# H38R01.net
KiCad netlist of a schematic drawn in EAGLE
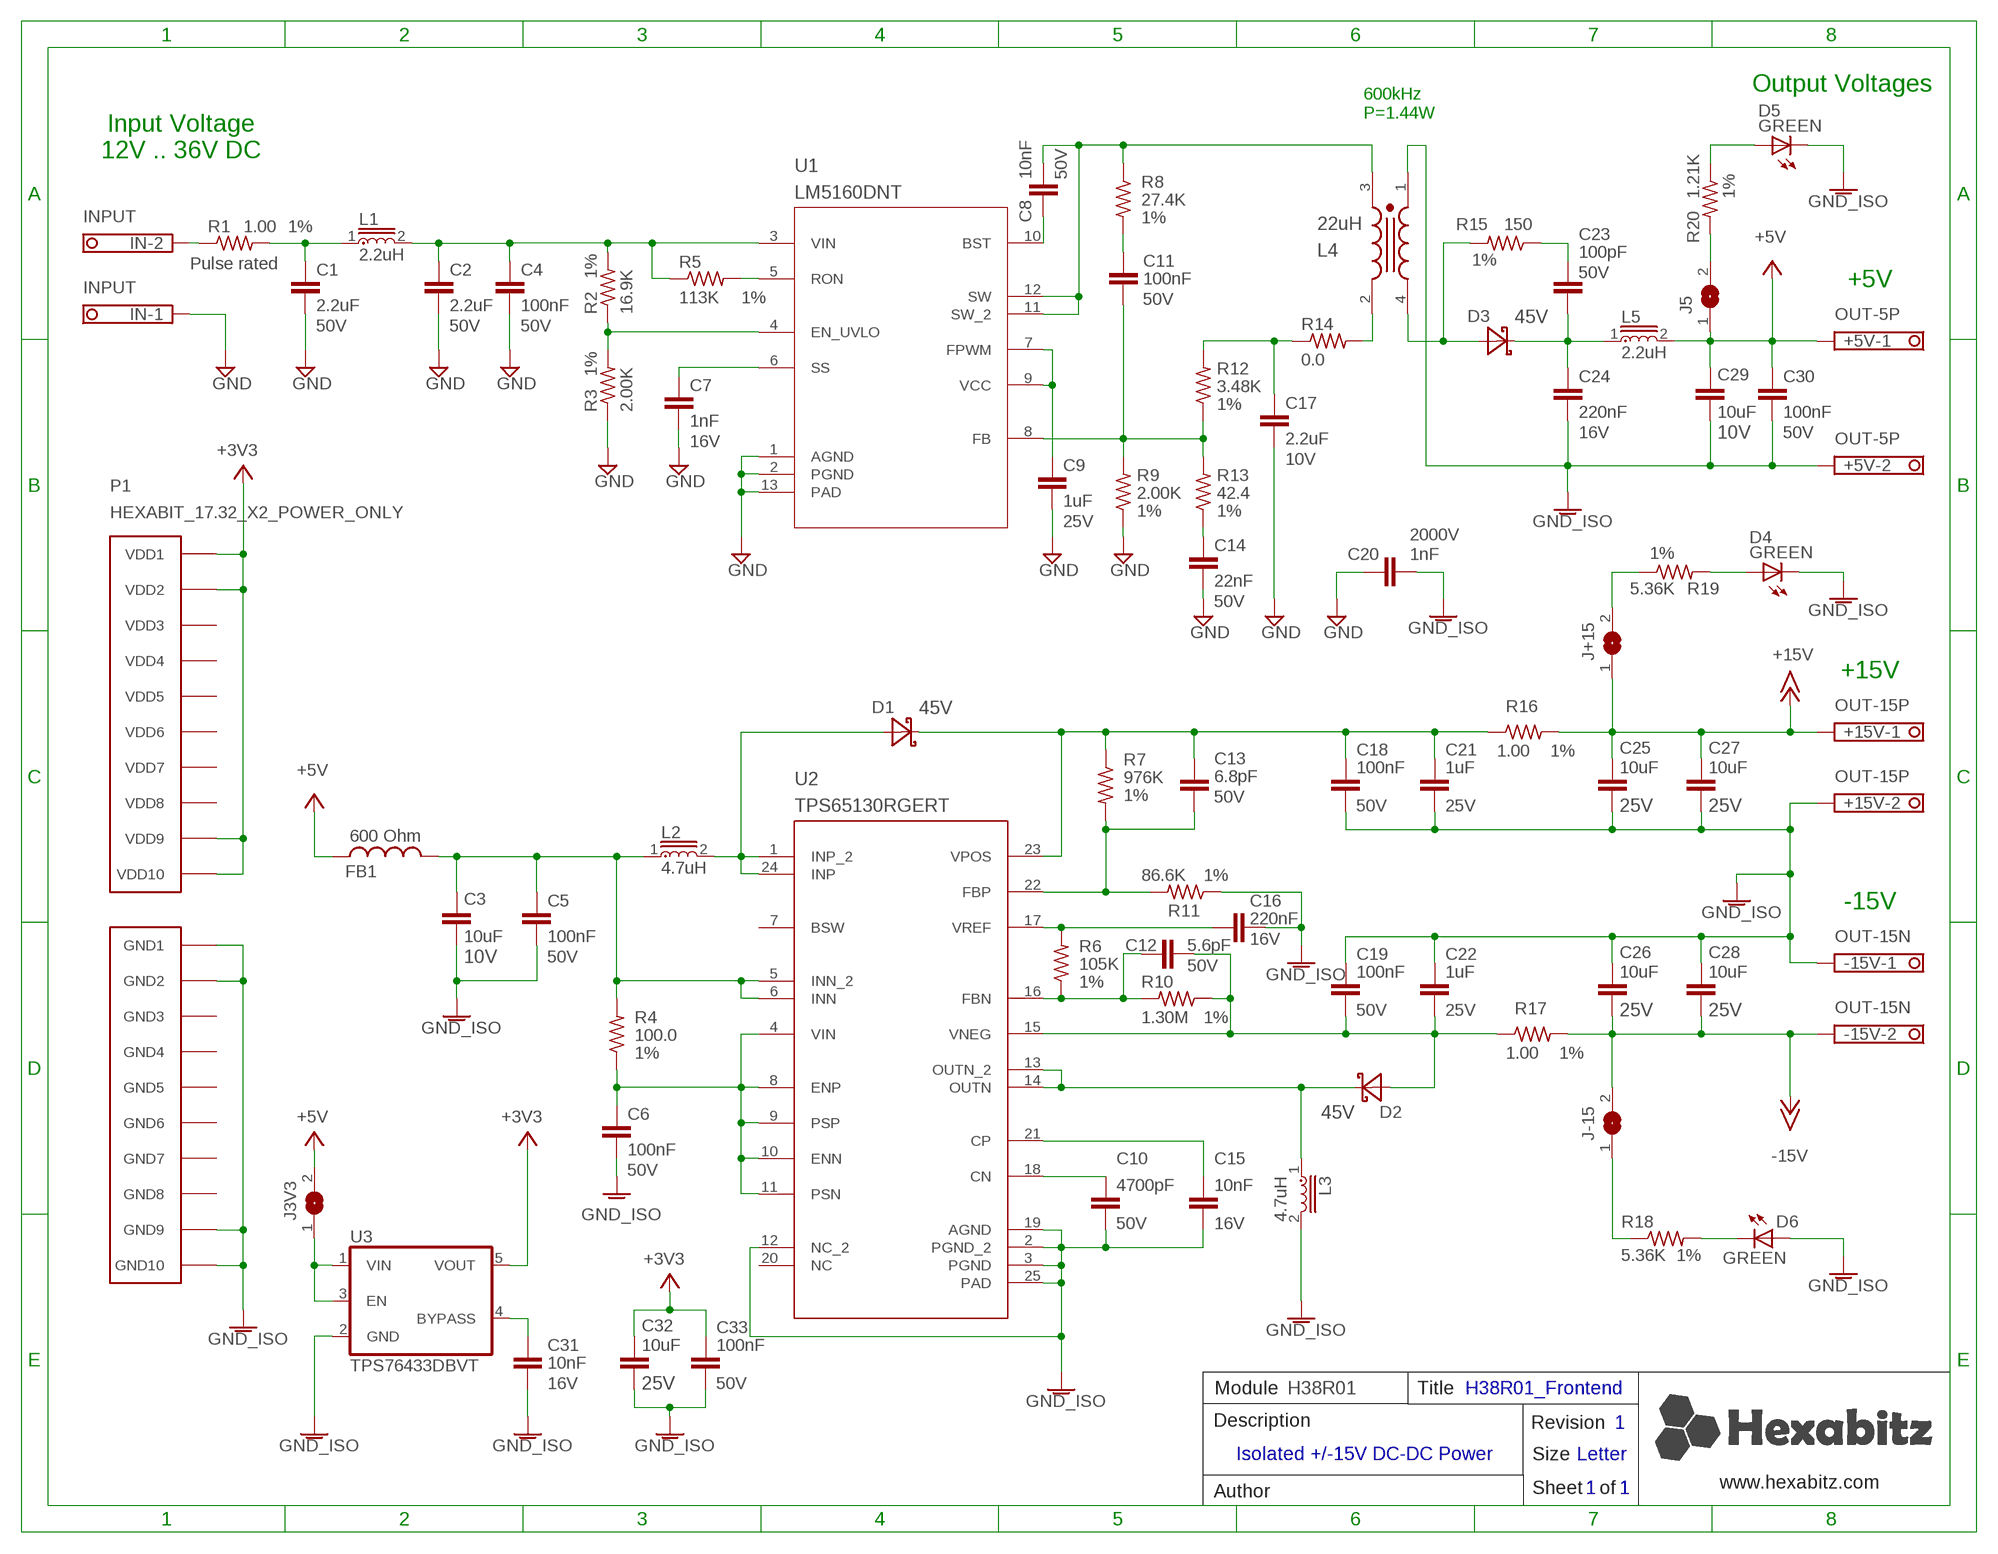
[diagram p0: schematic, sheet 1]

(export (version "E")
  (design (tool "Eeschema 10.0.6"))
  (components
    (comp (ref "+5V")
      (value "OUT-5P")
      (footprint "eagle-import:CON-PHOENIX-350_1751248")
      (fields (field (name "MPN") "1751251"))
      (libsource (lib "eagle-import") (part "CON-PHOENIX-350_1751248"))
    )
    (comp (ref "+15V")
      (value "OUT-15P")
      (footprint "eagle-import:CON-PHOENIX-350_1751248")
      (fields (field (name "MPN") "1751251"))
      (libsource (lib "eagle-import") (part "CON-PHOENIX-350_1751248"))
    )
    (comp (ref "-15V")
      (value "OUT-15N")
      (footprint "eagle-import:CON-PHOENIX-350_1751248")
      (fields (field (name "MPN") "1751251"))
      (libsource (lib "eagle-import") (part "CON-PHOENIX-350_1751248"))
    )
    (comp (ref "C1")
      (value "2.2uF")
      (footprint "eagle-import:C1206K")
      (fields (field (name "MPN") "UMK316B7225KD-T") (field (name "VOLTAGE") "50V"))
      (libsource (lib "eagle-import") (part "C-1206"))
    )
    (comp (ref "C2")
      (value "2.2uF")
      (footprint "eagle-import:C1206K")
      (fields (field (name "MPN") "UMK316B7225KD-T") (field (name "VOLTAGE") "50V"))
      (libsource (lib "eagle-import") (part "C-1206"))
    )
    (comp (ref "C3")
      (value "10uF")
      (footprint "eagle-import:C-0805")
      (fields
        (field (name "CAPACITANCE") "10uF")
        (field (name "MFN") "Würth Elektronik")
        (field (name "MPN") "885012207026")
        (field (name "OCTOPART_URL") "https://octopart.com/885012207026-w%C3%BCrth+elektronik-65419800?r=sp&s=PJ8-ZxRrRL-RXf1D2e7V7w ")
        (field (name "TOLERANCE") "10%")
        (field (name "VOLTAGE_RATING") "10V")
      )
      (libsource (lib "eagle-import") (part "C-0805"))
    )
    (comp (ref "C4")
      (value "100nF")
      (footprint "eagle-import:C-0603")
      (fields
        (field (name "CAPACITANCE") "100nF")
        (field (name "MFN") "TDK")
        (field (name "MPN") "C1608X7R1H104K")
        (field (name "OCTOPART_URL") "https://octopart.com/c1608x7r1h104k080aa-tdk-25947665?r=sp&s=vJ3_28x5RGekN18MBHqpKw")
        (field (name "TOLERANCE") "10%")
        (field (name "VOLTAGE_RATING") "50V")
      )
      (libsource (lib "eagle-import") (part "C-0603"))
    )
    (comp (ref "C5")
      (value "100nF")
      (footprint "eagle-import:C-0603")
      (fields
        (field (name "CAPACITANCE") "100nF")
        (field (name "MFN") "TDK")
        (field (name "MPN") "C1608X7R1H104K")
        (field (name "OCTOPART_URL") "https://octopart.com/c1608x7r1h104k080aa-tdk-25947665?r=sp&s=vJ3_28x5RGekN18MBHqpKw")
        (field (name "TOLERANCE") "10%")
        (field (name "VOLTAGE_RATING") "50V")
      )
      (libsource (lib "eagle-import") (part "C-0603"))
    )
    (comp (ref "C6")
      (value "100nF")
      (footprint "eagle-import:C-0603")
      (fields
        (field (name "CAPACITANCE") "100nF")
        (field (name "MFN") "TDK")
        (field (name "MPN") "C1608X7R1H104K")
        (field (name "OCTOPART_URL") "https://octopart.com/c1608x7r1h104k080aa-tdk-25947665?r=sp&s=vJ3_28x5RGekN18MBHqpKw")
        (field (name "TOLERANCE") "10%")
        (field (name "VOLTAGE_RATING") "50V")
      )
      (libsource (lib "eagle-import") (part "C-0603"))
    )
    (comp (ref "C7")
      (value "1nF")
      (footprint "eagle-import:C-0603")
      (fields
        (field (name "CAPACITANCE") "1nF")
        (field (name "MFN") "Würth Elektronik")
        (field (name "MPN") "885012206034")
        (field (name "OCTOPART_URL") "https://octopart.com/885012206034-w%C3%BCrth+elektronik-53914743?r=sp&s=3y92xzxLSKK6IudBxcGU8w")
        (field (name "TOLERANCE") "10%")
        (field (name "VOLTAGE_RATING") "16V")
      )
      (libsource (lib "eagle-import") (part "C-0603"))
    )
    (comp (ref "C8")
      (value "10nF")
      (footprint "eagle-import:C-0603")
      (fields
        (field (name "CAPACITANCE") "10nF")
        (field (name "MFN") "KEMET")
        (field (name "MPN") "C0603C103J5RACTU")
        (field (name "OCTOPART_URL") "https://octopart.com/c0603c103j5ractu-kemet-91371?r=sp&s=Kyc2xDn-SuWGmNLJldLSIQ")
        (field (name "TOLERANCE") "10%")
        (field (name "VOLTAGE_RATING") "50V")
      )
      (libsource (lib "eagle-import") (part "C-0603"))
    )
    (comp (ref "C9")
      (value "1uF")
      (footprint "eagle-import:C-0603")
      (fields
        (field (name "CAPACITANCE") "1uF")
        (field (name "MFN") "Taiyo Yuden")
        (field (name "MPN") "TMK107B7105KA-T")
        (field (name "OCTOPART_URL") "https://octopart.com/tmk107b7105ka-t-taiyo+yuden-20363789?r=sp&s=C0MvDSixSxq0oU7K_M5ppQ")
        (field (name "TOLERANCE") "10%")
        (field (name "VOLTAGE_RATING") "25V")
      )
      (libsource (lib "eagle-import") (part "C-0603"))
    )
    (comp (ref "C10")
      (value "4700pF")
      (footprint "eagle-import:C-0603")
      (fields
        (field (name "CAPACITANCE") "4700pF")
        (field (name "MFN") "Würth Elektronik")
        (field (name "MPN") "885012206087")
        (field (name "OCTOPART_URL") "https://octopart.com/885012206087-w%C3%BCrth+elektronik-53914796?r=sp&s=1K2nhhCgSUq-KN0bvB69Uw")
        (field (name "TOLERANCE") "10%")
        (field (name "VOLTAGE_RATING") "50V")
      )
      (libsource (lib "eagle-import") (part "C-0603"))
    )
    (comp (ref "C11")
      (value "100nF")
      (footprint "eagle-import:C-0603")
      (fields
        (field (name "CAPACITANCE") "100nF")
        (field (name "MFN") "TDK")
        (field (name "MPN") "C1608X7R1H104K")
        (field (name "OCTOPART_URL") "https://octopart.com/c1608x7r1h104k080aa-tdk-25947665?r=sp&s=vJ3_28x5RGekN18MBHqpKw")
        (field (name "TOLERANCE") "10%")
        (field (name "VOLTAGE_RATING") "50V")
      )
      (libsource (lib "eagle-import") (part "C-0603"))
    )
    (comp (ref "C12")
      (value "5.6pF")
      (footprint "eagle-import:C-0603")
      (fields
        (field (name "CAPACITANCE") "5.6pF")
        (field (name "MFN") "TDK")
        (field (name "MPN") "06035A5R6CAT2A")
        (field (name "OCTOPART_URL") "https://octopart.com/06035a5r6cat2a-avx-194782?r=sp&s=arSRmqwrS2KePu_erVaGmg")
        (field (name "TOLERANCE") "5%")
        (field (name "VOLTAGE_RATING") "50V")
      )
      (libsource (lib "eagle-import") (part "C-0603"))
    )
    (comp (ref "C13")
      (value "6.8pF")
      (footprint "eagle-import:C-0603")
      (fields
        (field (name "CAPACITANCE") "6.8pF")
        (field (name "MFN") "AVX")
        (field (name "MPN") "06035A6R8CAT2A")
        (field (name "OCTOPART_URL") "https://octopart.com/06035a6r8cat2a-avx-194783?r=sp&s=5-5NBtM6RDWLTSW9K30eVg")
        (field (name "TOLERANCE") "10%")
        (field (name "VOLTAGE_RATING") "50V")
      )
      (libsource (lib "eagle-import") (part "C-0603"))
    )
    (comp (ref "C14")
      (value "22nF")
      (footprint "eagle-import:C-0603")
      (fields
        (field (name "CAPACITANCE") "22nF")
        (field (name "MFN") "Murata")
        (field (name "MPN") "GRM188R71H223KA01D")
        (field (name "OCTOPART_URL") "https://octopart.com/grm188r71h223ka01d-murata-196232?r=sp&s=t23e6pi9S5yo9EHFMT_EKg")
        (field (name "TOLERANCE") "10%")
        (field (name "VOLTAGE_RATING") "50V")
      )
      (libsource (lib "eagle-import") (part "C-0603"))
    )
    (comp (ref "C15")
      (value "10nF")
      (footprint "eagle-import:C-0603")
      (fields
        (field (name "CAPACITANCE") "10nF")
        (field (name "MFN") "Würth Elektronik")
        (field (name "MPN") "885012206040")
        (field (name "OCTOPART_URL") "https://octopart.com/885012206040-w%C3%BCrth+elektronik-53914749?r=sp&s=G3_ezLbARM2-FohtMFECqg")
        (field (name "TOLERANCE") "10%")
        (field (name "VOLTAGE_RATING") "16V")
      )
      (libsource (lib "eagle-import") (part "C-0603"))
    )
    (comp (ref "C16")
      (value "220nF")
      (footprint "eagle-import:C-0603")
      (fields
        (field (name "CAPACITANCE") "220nF")
        (field (name "MFN") "Würth Elektronik")
        (field (name "MPN") "885012206048")
        (field (name "OCTOPART_URL") "https://octopart.com/885012206048-w%C3%BCrth+elektronik-53914757?r=sp&s=r2jVh1M7TTWSNtdrsMd35A")
        (field (name "TOLERANCE") "10%")
        (field (name "VOLTAGE_RATING") "16V")
      )
      (libsource (lib "eagle-import") (part "C-0603"))
    )
    (comp (ref "C17")
      (value "2.2uF")
      (footprint "eagle-import:C-0603")
      (fields
        (field (name "CAPACITANCE") "2.2uF")
        (field (name "MFN") "Murata")
        (field (name "MPN") "GRM188R71A225KE15D")
        (field (name "OCTOPART_URL") "https://octopart.com/grm188r71a225ke15d-murata-197889?r=sp&s=UhC5vs9xSQGkDEPPXrg6Ig")
        (field (name "TOLERANCE") "10%")
        (field (name "VOLTAGE_RATING") "10V")
      )
      (libsource (lib "eagle-import") (part "C-0603"))
    )
    (comp (ref "C18")
      (value "100nF")
      (footprint "eagle-import:C-0603")
      (fields
        (field (name "CAPACITANCE") "100nF")
        (field (name "MFN") "TDK")
        (field (name "MPN") "C1608X7R1H104K")
        (field (name "OCTOPART_URL") "https://octopart.com/c1608x7r1h104k080aa-tdk-25947665?r=sp&s=vJ3_28x5RGekN18MBHqpKw")
        (field (name "TOLERANCE") "10%")
        (field (name "VOLTAGE_RATING") "50V")
      )
      (libsource (lib "eagle-import") (part "C-0603"))
    )
    (comp (ref "C19")
      (value "100nF")
      (footprint "eagle-import:C-0603")
      (fields
        (field (name "CAPACITANCE") "100nF")
        (field (name "MFN") "TDK")
        (field (name "MPN") "C1608X7R1H104K")
        (field (name "OCTOPART_URL") "https://octopart.com/c1608x7r1h104k080aa-tdk-25947665?r=sp&s=vJ3_28x5RGekN18MBHqpKw")
        (field (name "TOLERANCE") "10%")
        (field (name "VOLTAGE_RATING") "50V")
      )
      (libsource (lib "eagle-import") (part "C-0603"))
    )
    (comp (ref "C20")
      (value "1nF")
      (footprint "eagle-import:C1206K")
      (fields (field (name "MPN") "202R18W102KV4E") (field (name "VOLTAGE") "2000V"))
      (libsource (lib "eagle-import") (part "C-1206"))
    )
    (comp (ref "C21")
      (value "1uF")
      (footprint "eagle-import:C-0603")
      (fields
        (field (name "CAPACITANCE") "1uF")
        (field (name "MFN") "Taiyo Yuden")
        (field (name "MPN") "TMK107B7105KA-T")
        (field (name "OCTOPART_URL") "https://octopart.com/tmk107b7105ka-t-taiyo+yuden-20363789?r=sp&s=C0MvDSixSxq0oU7K_M5ppQ")
        (field (name "TOLERANCE") "10%")
        (field (name "VOLTAGE_RATING") "25V")
      )
      (libsource (lib "eagle-import") (part "C-0603"))
    )
    (comp (ref "C22")
      (value "1uF")
      (footprint "eagle-import:C-0603")
      (fields
        (field (name "CAPACITANCE") "1uF")
        (field (name "MFN") "Taiyo Yuden")
        (field (name "MPN") "TMK107B7105KA-T")
        (field (name "OCTOPART_URL") "https://octopart.com/tmk107b7105ka-t-taiyo+yuden-20363789?r=sp&s=C0MvDSixSxq0oU7K_M5ppQ")
        (field (name "TOLERANCE") "10%")
        (field (name "VOLTAGE_RATING") "25V")
      )
      (libsource (lib "eagle-import") (part "C-0603"))
    )
    (comp (ref "C23")
      (value "100pF")
      (footprint "eagle-import:C-0603")
      (fields
        (field (name "CAPACITANCE") "100pF")
        (field (name "MFN") "KEMET")
        (field (name "MPN") "C0603C101J5GACTU")
        (field (name "OCTOPART_URL") "https://octopart.com/c0603c101j5gactu-kemet-100052?r=sp&s=G9Wafbc2Rs-t41DcITu08w")
        (field (name "TOLERANCE") "5%")
        (field (name "VOLTAGE_RATING") "50V")
      )
      (libsource (lib "eagle-import") (part "C-0603"))
    )
    (comp (ref "C24")
      (value "220nF")
      (footprint "eagle-import:C-0603")
      (fields
        (field (name "CAPACITANCE") "220nF")
        (field (name "MFN") "Würth Elektronik")
        (field (name "MPN") "885012206048")
        (field (name "OCTOPART_URL") "https://octopart.com/885012206048-w%C3%BCrth+elektronik-53914757?r=sp&s=r2jVh1M7TTWSNtdrsMd35A")
        (field (name "TOLERANCE") "10%")
        (field (name "VOLTAGE_RATING") "16V")
      )
      (libsource (lib "eagle-import") (part "C-0603"))
    )
    (comp (ref "C25")
      (value "10uF")
      (footprint "eagle-import:C-0805")
      (fields
        (field (name "CAPACITANCE") "10uF")
        (field (name "MFN") "Murata")
        (field (name "MPN") "GRM21BC71E106KE11L")
        (field (name "OCTOPART_URL") "https://octopart.com/grm21bc71e106ke11l-murata-51454492?r=sp&s=2Vde2RpCRyqy5YYMvYke3Q ")
        (field (name "TOLERANCE") "10%")
        (field (name "VOLTAGE_RATING") "25V")
      )
      (libsource (lib "eagle-import") (part "C-0805"))
    )
    (comp (ref "C26")
      (value "10uF")
      (footprint "eagle-import:C-0805")
      (fields
        (field (name "CAPACITANCE") "10uF")
        (field (name "MFN") "Murata")
        (field (name "MPN") "GRM21BC71E106KE11L")
        (field (name "OCTOPART_URL") "https://octopart.com/grm21bc71e106ke11l-murata-51454492?r=sp&s=2Vde2RpCRyqy5YYMvYke3Q ")
        (field (name "TOLERANCE") "10%")
        (field (name "VOLTAGE_RATING") "25V")
      )
      (libsource (lib "eagle-import") (part "C-0805"))
    )
    (comp (ref "C27")
      (value "10uF")
      (footprint "eagle-import:C-0805")
      (fields
        (field (name "CAPACITANCE") "10uF")
        (field (name "MFN") "Murata")
        (field (name "MPN") "GRM21BC71E106KE11L")
        (field (name "OCTOPART_URL") "https://octopart.com/grm21bc71e106ke11l-murata-51454492?r=sp&s=2Vde2RpCRyqy5YYMvYke3Q ")
        (field (name "TOLERANCE") "10%")
        (field (name "VOLTAGE_RATING") "25V")
      )
      (libsource (lib "eagle-import") (part "C-0805"))
    )
    (comp (ref "C28")
      (value "10uF")
      (footprint "eagle-import:C-0805")
      (fields
        (field (name "CAPACITANCE") "10uF")
        (field (name "MFN") "Murata")
        (field (name "MPN") "GRM21BC71E106KE11L")
        (field (name "OCTOPART_URL") "https://octopart.com/grm21bc71e106ke11l-murata-51454492?r=sp&s=2Vde2RpCRyqy5YYMvYke3Q")
        (field (name "TOLERANCE") "10%")
        (field (name "VOLTAGE_RATING") "25V")
      )
      (libsource (lib "eagle-import") (part "C-0805"))
    )
    (comp (ref "C29")
      (value "10uF")
      (footprint "eagle-import:C-0805")
      (fields
        (field (name "CAPACITANCE") "10uF")
        (field (name "MFN") "Würth Elektronik")
        (field (name "MPN") "885012207026")
        (field (name "OCTOPART_URL") "https://octopart.com/885012207026-w%C3%BCrth+elektronik-65419800?r=sp&s=PJ8-ZxRrRL-RXf1D2e7V7w")
        (field (name "TOLERANCE") "10%")
        (field (name "VOLTAGE_RATING") "10V")
      )
      (libsource (lib "eagle-import") (part "C-0805"))
    )
    (comp (ref "C30")
      (value "100nF")
      (footprint "eagle-import:C-0603")
      (fields
        (field (name "CAPACITANCE") "100nF")
        (field (name "MFN") "TDK")
        (field (name "MPN") "C1608X7R1H104K")
        (field (name "OCTOPART_URL") "https://octopart.com/c1608x7r1h104k080aa-tdk-25947665?r=sp&s=vJ3_28x5RGekN18MBHqpKw")
        (field (name "TOLERANCE") "10%")
        (field (name "VOLTAGE_RATING") "50V")
      )
      (libsource (lib "eagle-import") (part "C-0603"))
    )
    (comp (ref "C31")
      (value "10nF")
      (footprint "eagle-import:C-0603")
      (fields
        (field (name "CAPACITANCE") "10nF")
        (field (name "MFN") "Würth Elektronik")
        (field (name "MPN") "885012206040")
        (field (name "OCTOPART_URL") "https://octopart.com/885012206040-w%C3%BCrth+elektronik-53914749?r=sp&s=G3_ezLbARM2-FohtMFECqg")
        (field (name "TOLERANCE") "10%")
        (field (name "VOLTAGE_RATING") "16V")
      )
      (libsource (lib "eagle-import") (part "C-0603"))
    )
    (comp (ref "C32")
      (value "10uF")
      (footprint "eagle-import:C-0805")
      (fields
        (field (name "CAPACITANCE") "10uF")
        (field (name "MFN") "Murata")
        (field (name "MPN") "GRM21BC71E106KE11L")
        (field (name "OCTOPART_URL") "https://octopart.com/grm21bc71e106ke11l-murata-51454492?r=sp&s=2Vde2RpCRyqy5YYMvYke3Q")
        (field (name "TOLERANCE") "10%")
        (field (name "VOLTAGE_RATING") "25V")
      )
      (libsource (lib "eagle-import") (part "C-0805"))
    )
    (comp (ref "C33")
      (value "100nF")
      (footprint "eagle-import:C-0603")
      (fields
        (field (name "CAPACITANCE") "100nF")
        (field (name "MFN") "TDK")
        (field (name "MPN") "C1608X7R1H104K")
        (field (name "OCTOPART_URL") "https://octopart.com/c1608x7r1h104k080aa-tdk-25947665?r=sp&s=vJ3_28x5RGekN18MBHqpKw")
        (field (name "TOLERANCE") "10%")
        (field (name "VOLTAGE_RATING") "50V")
      )
      (libsource (lib "eagle-import") (part "C-0603"))
    )
    (comp (ref "D1")
      (value "DIOD-SOD-123")
      (footprint "eagle-import:SOD123")
      (fields
        (field (name "MFN") "ON Semiconductor")
        (field (name "MPN") "NTS245SFT1G")
        (field (name "OCTOPART_URL") "https://octopart.com/nts245sft1g-on+semiconductor-53638116?r=sp&s=Zo8Z59f0QcynsgZ2PtBRwg")
        (field (name "VOLTAGE_RATING_DC") "45V")
      )
      (libsource (lib "eagle-import") (part "DIOD-SOD-123"))
    )
    (comp (ref "D2")
      (value "DIOD-SOD-123")
      (footprint "eagle-import:SOD123")
      (fields
        (field (name "MFN") "ON Semiconductor")
        (field (name "MPN") "NTS245SFT1G")
        (field (name "OCTOPART_URL") "https://octopart.com/nts245sft1g-on+semiconductor-53638116?r=sp&s=Zo8Z59f0QcynsgZ2PtBRwg")
        (field (name "VOLTAGE_RATING_DC") "45V")
      )
      (libsource (lib "eagle-import") (part "DIOD-SOD-123"))
    )
    (comp (ref "D3")
      (value "DIOD-SOD-123")
      (footprint "eagle-import:SOD123")
      (fields
        (field (name "MFN") "ON Semiconductor")
        (field (name "MPN") "NTS245SFT1G")
        (field (name "OCTOPART_URL") "https://octopart.com/nts245sft1g-on+semiconductor-53638116?r=sp&s=Zo8Z59f0QcynsgZ2PtBRwg")
        (field (name "VOLTAGE_RATING_DC") "45V")
      )
      (libsource (lib "eagle-import") (part "DIOD-SOD-123"))
    )
    (comp (ref "D4")
      (value "GREEN")
      (footprint "eagle-import:VLMS1300-GS08")
      (fields (field (name "MPN") "VLMTG1300-GS08"))
      (libsource (lib "eagle-import") (part "VLMTG1300-GS08"))
    )
    (comp (ref "D5")
      (value "GREEN")
      (footprint "eagle-import:VLMS1300-GS08")
      (fields (field (name "MPN") "VLMTG1300-GS08"))
      (libsource (lib "eagle-import") (part "VLMTG1300-GS08"))
    )
    (comp (ref "D6")
      (value "GREEN")
      (footprint "eagle-import:VLMS1300-GS08")
      (fields (field (name "MPN") "VLMTG1300-GS08"))
      (libsource (lib "eagle-import") (part "VLMTG1300-GS08"))
    )
    (comp (ref "FB1")
      (value "600 Ohm")
      (footprint "eagle-import:FB-0603")
      (fields
        (field (name "MFN") "Murata")
        (field (name "MPN") "BLM18KG601SN1D")
        (field (name "OCTOPART_URL") "https://octopart.com/blm18kg601sn1d-murata-12276433?r=sp&s=hc41AUOpRWisdZqqWWZOxA")
      )
      (libsource (lib "eagle-import") (part "FB-0603"))
    )
    (comp (ref "IN")
      (value "INPUT")
      (footprint "eagle-import:CON-PHOENIX-350_1751248")
      (fields (field (name "MPN") "1751251"))
      (libsource (lib "eagle-import") (part "CON-PHOENIX-350_1751248"))
    )
    (comp (ref "J+15")
      (value "SJ")
      (footprint "eagle-import:SJ")
      (libsource (lib "eagle-import") (part "SJ"))
    )
    (comp (ref "J-15")
      (value "SJ")
      (footprint "eagle-import:SJ")
      (libsource (lib "eagle-import") (part "SJ"))
    )
    (comp (ref "J3V3")
      (value "SJ")
      (footprint "eagle-import:SJ")
      (libsource (lib "eagle-import") (part "SJ"))
    )
    (comp (ref "J5") (value "SJ") (footprint "eagle-import:SJ") (libsource (lib "eagle-import") (part "SJ")))
    (comp (ref "L1")
      (value "2.2uH")
      (footprint "eagle-import:C-0603")
      (fields (field (name "MPN") "LQM18PN2R2MFHD"))
      (libsource (lib "eagle-import") (part "LQM18PN2R2MFHD"))
    )
    (comp (ref "L2")
      (value "4.7uH")
      (footprint "eagle-import:WUERTH_ELEKTRONIK_74404024100_0")
      (fields
        (field (name "MF") "Wuerth Elektronik")
        (field (name "MPN") "74404024100")
        (field (name "INDUCTANCE") "4.7μH")
        (field (name "MPN_1") "74404024047")
        (field (name "OCTOPART_URL") "https://octopart.com/74404024047-w%C3%BCrth+elektronik-46948230?r=sp")
      )
      (libsource (lib "eagle-import") (part "WUERTH_ELEKTRONIK_74404024100WUERTH_ELEKTRONIK_74404024100_0_0"))
    )
    (comp (ref "L3")
      (value "4.7uH")
      (footprint "eagle-import:WUERTH_ELEKTRONIK_74404024100_0")
      (fields
        (field (name "MF") "Wuerth Elektronik")
        (field (name "MPN") "74404024100")
        (field (name "INDUCTANCE") "4.7μH")
        (field (name "MPN_1") "74404024047")
        (field (name "OCTOPART_URL") "https://octopart.com/74404024047-w%C3%BCrth+elektronik-46948230?r=sp")
      )
      (libsource (lib "eagle-import") (part "WUERTH_ELEKTRONIK_74404024100WUERTH_ELEKTRONIK_74404024100_0_0"))
    )
    (comp (ref "L4")
      (value "22uH")
      (footprint "eagle-import:WUERTH_ELEKTRONIK_74489430220_0")
      (fields (field (name "MF") "Wuerth Elektronik") (field (name "MPN") "74489430220"))
      (libsource (lib "eagle-import") (part "WUERTH_ELEKTRONIK_74489430220WUERTH_ELEKTRONIK_74489430220_0_0"))
    )
    (comp (ref "L5")
      (value "2.2uH")
      (footprint "eagle-import:C-0603")
      (fields (field (name "MPN") "LQM18PN2R2MFHD"))
      (libsource (lib "eagle-import") (part "LQM18PN2R2MFHD"))
    )
    (comp (ref "P1")
      (value "HEXABIT_17.32_X2_POWER_ONLY")
      (footprint "eagle-import:HEXABIT_17.32_X2_POWER_ONLY")
      (libsource (lib "eagle-import") (part "HEXABIT_?_X2_POWER_ONLY17.32"))
    )
    (comp (ref "R1")
      (value "1.00")
      (footprint "eagle-import:R-0603")
      (fields
        (field (name "MFN") "Vishay")
        (field (name "MPN") "RCS06031R00FKEA")
        (field (name "OCTOPART_URL") "https://octopart.com/rcs06031r00fkea-vishay-75198106?r=sp")
        (field (name "RESISTANCE") "1.00")
        (field (name "TOLERANCE") "1%")
      )
      (libsource (lib "eagle-import") (part "R-0603"))
    )
    (comp (ref "R2")
      (value "16.9K")
      (footprint "eagle-import:R-0603")
      (fields
        (field (name "MFN") "Vishay")
        (field (name "MPN") "CRCW060316K9FKEA")
        (field (name "OCTOPART_URL") "https://octopart.com/crcw060316k9fkea-vishay-39809405?r=sp&s=gpyoC5sESS275Bx1L_ovfA")
        (field (name "RESISTANCE") "16.9K")
        (field (name "TOLERANCE") "1%")
      )
      (libsource (lib "eagle-import") (part "R-0603"))
    )
    (comp (ref "R3")
      (value "2.00K")
      (footprint "eagle-import:R-0603")
      (fields
        (field (name "MFN") "Vishay")
        (field (name "MPN") "CRCW06032K00FKEA")
        (field (name "OCTOPART_URL") "https://octopart.com/crcw06032k00fkea-vishay-39455515?r=sp&s=oLMBsKnqSyiGxb37P4YGRQ")
        (field (name "RESISTANCE") "2.00k")
        (field (name "TOLERANCE") "1%")
      )
      (libsource (lib "eagle-import") (part "R-0603"))
    )
    (comp (ref "R4")
      (value "100.0")
      (footprint "eagle-import:R-0603")
      (fields
        (field (name "MFN") "Vishay")
        (field (name "MPN") "CRCW0603100RFKEA")
        (field (name "OCTOPART_URL") "https://octopart.com/crcw0603100rfkea-vishay-39454046?r=sp&s=ZCLXy-8WTNaYdj0NMUzO0A")
        (field (name "RESISTANCE") "100.0")
        (field (name "TOLERANCE") "1%")
      )
      (libsource (lib "eagle-import") (part "R-0603"))
    )
    (comp (ref "R5")
      (value "113K")
      (footprint "eagle-import:R-0603")
      (fields
        (field (name "MFN") "Vishay")
        (field (name "MPN") "CRCW0603113KFKEA")
        (field (name "OCTOPART_URL") "https://octopart.com/crcw0603113kfkea-vishay-39817257?r=sp&s=CTaWAi24RJSm7_6d5HDAcw")
        (field (name "RESISTANCE") "113K")
        (field (name "TOLERANCE") "1%")
      )
      (libsource (lib "eagle-import") (part "R-0603"))
    )
    (comp (ref "R6")
      (value "105K")
      (footprint "eagle-import:R-0603")
      (fields
        (field (name "MFN") "Vishay")
        (field (name "MPN") "CRCW0603105KFKEA")
        (field (name "OCTOPART_URL") "https://octopart.com/crcw0603105kfkea-vishay-39783419?r=sp&s=m57LqOW9SZi8auMTWgZAuA")
        (field (name "RESISTANCE") "105K")
        (field (name "TOLERANCE") "1%")
      )
      (libsource (lib "eagle-import") (part "R-0603"))
    )
    (comp (ref "R7")
      (value "976K")
      (footprint "eagle-import:R-0603")
      (fields
        (field (name "MFN") "Vishay")
        (field (name "MPN") "CRCW0603976KFKEA")
        (field (name "OCTOPART_URL") "https://octopart.com/crcw0603976kfkea-vishay-39847458?r=sp&s=cUxC9lyxRzee74EppCoygA")
        (field (name "RESISTANCE") "976K")
        (field (name "TOLERANCE") "1%")
      )
      (libsource (lib "eagle-import") (part "R-0603"))
    )
    (comp (ref "R8")
      (value "27.4K")
      (footprint "eagle-import:R-0603")
      (fields
        (field (name "MFN") "Vishay")
        (field (name "MPN") "CRCW060327K4FKEA")
        (field (name "OCTOPART_URL") "https://octopart.com/crcw060327k4fkea-vishay-40950191?r=sp&s=-sh_flwyTnabpVfO2SO3MQ")
        (field (name "RESISTANCE") "27.4K")
        (field (name "TOLERANCE") "1%")
      )
      (libsource (lib "eagle-import") (part "R-0603"))
    )
    (comp (ref "R9")
      (value "2.00K")
      (footprint "eagle-import:R-0603")
      (fields
        (field (name "MFN") "Vishay")
        (field (name "MPN") "CRCW06032K00FKEA")
        (field (name "OCTOPART_URL") "https://octopart.com/crcw06032k00fkea-vishay-39455515?r=sp&s=oLMBsKnqSyiGxb37P4YGRQ")
        (field (name "RESISTANCE") "2.00k")
        (field (name "TOLERANCE") "1%")
      )
      (libsource (lib "eagle-import") (part "R-0603"))
    )
    (comp (ref "R10")
      (value "1.30M")
      (footprint "eagle-import:R-0603")
      (fields
        (field (name "MFN") "Vishay")
        (field (name "MPN") "CRCW06031M30FKEA")
        (field (name "OCTOPART_URL") "https://octopart.com/crcw06031m30fkea-vishay-39601140?r=sp&s=IFmbrVO2QdmVcSmXO7E1AA")
        (field (name "RESISTANCE") "1.30M")
        (field (name "TOLERANCE") "1%")
      )
      (libsource (lib "eagle-import") (part "R-0603"))
    )
    (comp (ref "R11")
      (value "86.6K")
      (footprint "eagle-import:R-0603")
      (fields
        (field (name "MFN") "Vishay")
        (field (name "MPN") "CRCW060386K6FKEA")
        (field (name "OCTOPART_URL") "https://octopart.com/crcw060386k6fkea-vishay-39809057?r=sp&s=kiKKot43Sa6nkjOnoApb7Q")
        (field (name "RESISTANCE") "86.6K")
        (field (name "TOLERANCE") "1%")
      )
      (libsource (lib "eagle-import") (part "R-0603"))
    )
    (comp (ref "R12")
      (value "3.48K")
      (footprint "eagle-import:R-0603")
      (fields
        (field (name "MFN") "Vishay")
        (field (name "MPN") "CRCW06033K48FKEA")
        (field (name "OCTOPART_URL") "https://octopart.com/crcw06033k48fkea-vishay-39806638?r=sp&s=N5g7S2AyTDmMWBX-_wGc6Q")
        (field (name "RESISTANCE") "3.48K")
        (field (name "TOLERANCE") "1%")
      )
      (libsource (lib "eagle-import") (part "R-0603"))
    )
    (comp (ref "R13")
      (value "42.4")
      (footprint "eagle-import:R-0603")
      (fields
        (field (name "MFN") "Vishay")
        (field (name "MPN") "CRCW060342R2FKEA")
        (field (name "OCTOPART_URL") "https://octopart.com/crcw060342r2fkea-vishay-39808977?r=sp&s=-XoBdwS-TmODK1i1WGs3Gw")
        (field (name "RESISTANCE") "42.2R")
        (field (name "TOLERANCE") "1%")
      )
      (libsource (lib "eagle-import") (part "R-0603"))
    )
    (comp (ref "R14")
      (value "0.0")
      (footprint "eagle-import:R-0603")
      (fields
        (field (name "MFN") "Panasonic")
        (field (name "MPN") "ERJ-3GEY0R00V")
        (field (name "OCTOPART_URL") "https://octopart.com/erj-3gey0r00v-panasonic-55389238?r=sp&s=8dmrTZyCS32IAujh55Hh-g")
        (field (name "RESISTANCE") "0.0R")
        (field (name "TOLERANCE") "5%")
      )
      (libsource (lib "eagle-import") (part "R-0603"))
    )
    (comp (ref "R15")
      (value "150")
      (footprint "eagle-import:R-0603")
      (fields
        (field (name "MFN") "Vishay")
        (field (name "MPN") "CRCW0603150RFKEA")
        (field (name "OCTOPART_URL") "https://octopart.com/crcw0603150rfkea-vishay-39455211?r=sp&s=fhZ4fTqDSW-fVK_X4mehlA")
        (field (name "RESISTANCE") "150R")
        (field (name "TOLERANCE") "1%")
      )
      (libsource (lib "eagle-import") (part "R-0603"))
    )
    (comp (ref "R16")
      (value "1.00")
      (footprint "eagle-import:R-0603")
      (fields
        (field (name "MFN") "Vishay-Dale")
        (field (name "MPN") "CRCW06031R00FKEA")
        (field (name "OCTOPART_URL") "https://octopart.com/crcw06031r00fkea-vishay-39713722?r=sp&s=biXSlGylTBiwPOCcABx_kA")
        (field (name "RESISTANCE") "1.00")
        (field (name "TOLERANCE") "1%")
      )
      (libsource (lib "eagle-import") (part "R-0603"))
    )
    (comp (ref "R17")
      (value "1.00")
      (footprint "eagle-import:R-0603")
      (fields
        (field (name "MFN") "Vishay-Dale")
        (field (name "MPN") "CRCW06031R00FKEA")
        (field (name "OCTOPART_URL") "https://octopart.com/crcw06031r00fkea-vishay-39713722?r=sp&s=biXSlGylTBiwPOCcABx_kA")
        (field (name "RESISTANCE") "1.00")
        (field (name "TOLERANCE") "1%")
      )
      (libsource (lib "eagle-import") (part "R-0603"))
    )
    (comp (ref "R18")
      (value "5.36K")
      (footprint "eagle-import:R-0603")
      (fields
        (field (name "MFN") "Vishay")
        (field (name "MPN") "CRCW06035K36FKEA")
        (field (name "OCTOPART_URL") "https://octopart.com/crcw06035k36fkea-vishay-39850082?r=sp&s=UzQdyXKeQlK-zUZHNwTiSQ")
        (field (name "RESISTANCE") "5.36K")
        (field (name "TOLERANCE") "1%")
      )
      (libsource (lib "eagle-import") (part "R-0603"))
    )
    (comp (ref "R19")
      (value "5.36K")
      (footprint "eagle-import:R-0603")
      (fields
        (field (name "MFN") "Vishay")
        (field (name "MPN") "CRCW06035K36FKEA")
        (field (name "OCTOPART_URL") "https://octopart.com/crcw06035k36fkea-vishay-39850082?r=sp&s=UzQdyXKeQlK-zUZHNwTiSQ")
        (field (name "RESISTANCE") "5.36K")
        (field (name "TOLERANCE") "1%")
      )
      (libsource (lib "eagle-import") (part "R-0603"))
    )
    (comp (ref "R20")
      (value "1.21K")
      (footprint "eagle-import:R-0603")
      (fields
        (field (name "MFN") "Vishay")
        (field (name "MPN") "CRCW06031K21FKEA")
        (field (name "OCTOPART_URL") "https://octopart.com/crcw06031k21fkea-vishay-39455541?r=sp&s=DmmN7huOS0CziwVau3vt0g")
        (field (name "RESISTANCE") "1.21K")
        (field (name "TOLERANCE") "1%")
      )
      (libsource (lib "eagle-import") (part "R-0603"))
    )
    (comp (ref "U1")
      (value "LM5160DNT")
      (footprint "eagle-import:DNT0012B")
      (fields (field (name "MANUFACTURER") "Texas Instruments"))
      (libsource (lib "eagle-import") (part "LM5160DNT"))
    )
    (comp (ref "U2")
      (value "TPS65130RGERT")
      (footprint "eagle-import:RGE0024B_NV")
      (fields
        (field (name "ALTERNATE_PARTNUMBER") "TPS65130RGET")
        (field (name "MANUFACTURER") "Texas Instruments")
        (field (name "PARTNUMBER") "TPS65130RGER")
      )
      (libsource (lib "eagle-import") (part "TPS65130RGERT"))
    )
    (comp (ref "U3")
      (value "TPS76433DBVT")
      (footprint "eagle-import:SOT25")
      (libsource (lib "eagle-import") (part "TPS764DBVT33"))
    )
  )
  (nets
    (net (code "1") (name "+3V3") (class "Default")
      (node (ref "C32") (pin "1") (pinfunction "1_1") (pintype "passive"))
      (node (ref "C33") (pin "1") (pinfunction "1_1") (pintype "passive"))
      (node (ref "P1") (pin "PAD_PU11") (pinfunction "VDD1_PAD_PU11") (pintype "power_in"))
      (node (ref "P1") (pin "PAD_PU12") (pinfunction "VDD2_PAD_PU12") (pintype "power_in"))
      (node (ref "P1") (pin "PAD_PU19") (pinfunction "VDD9_PAD_PU19") (pintype "power_in"))
      (node (ref "P1") (pin "PAD_PU20") (pinfunction "VDD10_PAD_PU20") (pintype "power_in"))
      (node (ref "U3") (pin "5") (pinfunction "VOUT_5") (pintype "passive"))
    )
    (net (code "2") (name "+5V") (class "Default")
      (node (ref "+5V") (pin "1") (pinfunction "K_1") (pintype "passive"))
      (node (ref "C29") (pin "1") (pinfunction "1_1") (pintype "passive"))
      (node (ref "C30") (pin "1") (pinfunction "1_1") (pintype "passive"))
      (node (ref "FB1") (pin "1") (pinfunction "1_1") (pintype "passive"))
      (node (ref "J3V3") (pin "2") (pinfunction "2_2") (pintype "passive"))
      (node (ref "J5") (pin "1") (pinfunction "1_1") (pintype "passive"))
      (node (ref "L5") (pin "2") (pinfunction "2_2") (pintype "passive"))
    )
    (net (code "3") (name "+15V") (class "Default")
      (node (ref "+15V") (pin "1") (pinfunction "K_1") (pintype "passive"))
      (node (ref "C25") (pin "1") (pinfunction "1_1") (pintype "passive"))
      (node (ref "C27") (pin "1") (pinfunction "1_1") (pintype "passive"))
      (node (ref "J+15") (pin "1") (pinfunction "1_1") (pintype "passive"))
      (node (ref "R16") (pin "2") (pinfunction "2_2") (pintype "passive"))
    )
    (net (code "4") (name "-15V") (class "Default")
      (node (ref "-15V") (pin "2") (pinfunction "K_2") (pintype "passive"))
      (node (ref "C26") (pin "2") (pinfunction "2_2") (pintype "passive"))
      (node (ref "C28") (pin "2") (pinfunction "2_2") (pintype "passive"))
      (node (ref "J-15") (pin "2") (pinfunction "2_2") (pintype "passive"))
      (node (ref "R17") (pin "2") (pinfunction "2_2") (pintype "passive"))
    )
    (net (code "5") (name "/GND3") (class "Default")
      (node (ref "P1") (pin "PAD_PD13") (pinfunction "GND3_PAD_PD13") (pintype "power_in"))
    )
    (net (code "6") (name "/GND4") (class "Default")
      (node (ref "P1") (pin "PAD_PD14") (pinfunction "GND4_PAD_PD14") (pintype "power_in"))
    )
    (net (code "7") (name "/GND5") (class "Default")
      (node (ref "P1") (pin "PAD_PD15") (pinfunction "GND5_PAD_PD15") (pintype "power_in"))
    )
    (net (code "8") (name "/GND6") (class "Default")
      (node (ref "P1") (pin "PAD_PD16") (pinfunction "GND6_PAD_PD16") (pintype "power_in"))
    )
    (net (code "9") (name "/GND7") (class "Default")
      (node (ref "P1") (pin "PAD_PD17") (pinfunction "GND7_PAD_PD17") (pintype "power_in"))
    )
    (net (code "10") (name "/GND8") (class "Default")
      (node (ref "P1") (pin "PAD_PD18") (pinfunction "GND8_PAD_PD18") (pintype "power_in"))
    )
    (net (code "11") (name "/VDD3") (class "Default")
      (node (ref "P1") (pin "PAD_PU13") (pinfunction "VDD3_PAD_PU13") (pintype "power_in"))
    )
    (net (code "12") (name "/VDD4") (class "Default")
      (node (ref "P1") (pin "PAD_PU14") (pinfunction "VDD4_PAD_PU14") (pintype "power_in"))
    )
    (net (code "13") (name "/VDD5") (class "Default")
      (node (ref "P1") (pin "PAD_PU15") (pinfunction "VDD5_PAD_PU15") (pintype "power_in"))
    )
    (net (code "14") (name "/VDD6") (class "Default")
      (node (ref "P1") (pin "PAD_PU16") (pinfunction "VDD6_PAD_PU16") (pintype "power_in"))
    )
    (net (code "15") (name "/VDD7") (class "Default")
      (node (ref "P1") (pin "PAD_PU17") (pinfunction "VDD7_PAD_PU17") (pintype "power_in"))
    )
    (net (code "16") (name "/VDD8") (class "Default")
      (node (ref "P1") (pin "PAD_PU18") (pinfunction "VDD8_PAD_PU18") (pintype "power_in"))
    )
    (net (code "17") (name "GND") (class "Default")
      (node (ref "C1") (pin "2") (pinfunction "2_2") (pintype "passive"))
      (node (ref "C14") (pin "2") (pinfunction "2_2") (pintype "passive"))
      (node (ref "C17") (pin "2") (pinfunction "2_2") (pintype "passive"))
      (node (ref "C2") (pin "2") (pinfunction "2_2") (pintype "passive"))
      (node (ref "C20") (pin "1") (pinfunction "1_1") (pintype "passive"))
      (node (ref "C4") (pin "2") (pinfunction "2_2") (pintype "passive"))
      (node (ref "C7") (pin "2") (pinfunction "2_2") (pintype "passive"))
      (node (ref "C9") (pin "2") (pinfunction "2_2") (pintype "passive"))
      (node (ref "IN") (pin "1") (pinfunction "K_1") (pintype "passive"))
      (node (ref "R3") (pin "1") (pinfunction "1_1") (pintype "passive"))
      (node (ref "R9") (pin "1") (pinfunction "1_1") (pintype "passive"))
      (node (ref "U1") (pin "1") (pinfunction "AGND_1") (pintype "power_in"))
      (node (ref "U1") (pin "13") (pinfunction "PAD_13") (pintype "power_in"))
      (node (ref "U1") (pin "2") (pinfunction "PGND_2") (pintype "power_in"))
    )
    (net (code "18") (name "GND_ISO") (class "Default")
      (node (ref "+15V") (pin "2") (pinfunction "K_2") (pintype "passive"))
      (node (ref "+5V") (pin "2") (pinfunction "K_2") (pintype "passive"))
      (node (ref "-15V") (pin "1") (pinfunction "K_1") (pintype "passive"))
      (node (ref "C10") (pin "2") (pinfunction "2_2") (pintype "passive"))
      (node (ref "C15") (pin "2") (pinfunction "2_2") (pintype "passive"))
      (node (ref "C16") (pin "2") (pinfunction "2_2") (pintype "passive"))
      (node (ref "C18") (pin "2") (pinfunction "2_2") (pintype "passive"))
      (node (ref "C19") (pin "1") (pinfunction "1_1") (pintype "passive"))
      (node (ref "C20") (pin "2") (pinfunction "2_2") (pintype "passive"))
      (node (ref "C21") (pin "2") (pinfunction "2_2") (pintype "passive"))
      (node (ref "C22") (pin "1") (pinfunction "1_1") (pintype "passive"))
      (node (ref "C24") (pin "2") (pinfunction "2_2") (pintype "passive"))
      (node (ref "C25") (pin "2") (pinfunction "2_2") (pintype "passive"))
      (node (ref "C26") (pin "1") (pinfunction "1_1") (pintype "passive"))
      (node (ref "C27") (pin "2") (pinfunction "2_2") (pintype "passive"))
      (node (ref "C28") (pin "1") (pinfunction "1_1") (pintype "passive"))
      (node (ref "C29") (pin "2") (pinfunction "2_2") (pintype "passive"))
      (node (ref "C3") (pin "2") (pinfunction "2_2") (pintype "passive"))
      (node (ref "C30") (pin "2") (pinfunction "2_2") (pintype "passive"))
      (node (ref "C31") (pin "2") (pinfunction "2_2") (pintype "passive"))
      (node (ref "C32") (pin "2") (pinfunction "2_2") (pintype "passive"))
      (node (ref "C33") (pin "2") (pinfunction "2_2") (pintype "passive"))
      (node (ref "C5") (pin "2") (pinfunction "2_2") (pintype "passive"))
      (node (ref "C6") (pin "2") (pinfunction "2_2") (pintype "passive"))
      (node (ref "D4") (pin "C") (pinfunction "C_C") (pintype "passive"))
      (node (ref "D5") (pin "C") (pinfunction "C_C") (pintype "passive"))
      (node (ref "D6") (pin "A") (pinfunction "A_A") (pintype "passive"))
      (node (ref "L3") (pin "2") (pinfunction "2_2") (pintype "passive"))
      (node (ref "L4") (pin "1") (pinfunction "1_1") (pintype "passive"))
      (node (ref "P1") (pin "PAD_PD11") (pinfunction "GND1_PAD_PD11") (pintype "power_in"))
      (node (ref "P1") (pin "PAD_PD12") (pinfunction "GND2_PAD_PD12") (pintype "power_in"))
      (node (ref "P1") (pin "PAD_PD19") (pinfunction "GND9_PAD_PD19") (pintype "power_in"))
      (node (ref "P1") (pin "PAD_PD20") (pinfunction "GND10_PAD_PD20") (pintype "power_in"))
      (node (ref "R11") (pin "1") (pinfunction "1_1") (pintype "passive"))
      (node (ref "U2") (pin "12") (pinfunction "NC_2_12") (pintype "passive"))
      (node (ref "U2") (pin "19") (pinfunction "AGND_19") (pintype "power_in"))
      (node (ref "U2") (pin "2") (pinfunction "PGND_2_2") (pintype "power_in"))
      (node (ref "U2") (pin "25") (pinfunction "PAD_25") (pintype "power_in"))
      (node (ref "U2") (pin "3") (pinfunction "PGND_3") (pintype "power_in"))
      (node (ref "U3") (pin "2") (pinfunction "GND_2") (pintype "passive"))
    )
    (net (code "19") (name "Net-(C1-Pad1)") (class "Default")
      (node (ref "C1") (pin "1") (pinfunction "1_1") (pintype "passive"))
      (node (ref "L1") (pin "1") (pinfunction "1_1") (pintype "passive"))
      (node (ref "R1") (pin "2") (pinfunction "2_2") (pintype "passive"))
    )
    (net (code "20") (name "Net-(C11-Pad1)") (class "Default")
      (node (ref "C11") (pin "1") (pinfunction "1_1") (pintype "passive"))
      (node (ref "R8") (pin "2") (pinfunction "2_2") (pintype "passive"))
    )
    (net (code "21") (name "Net-(C14-Pad1)") (class "Default")
      (node (ref "C14") (pin "1") (pinfunction "1_1") (pintype "passive"))
      (node (ref "R13") (pin "1") (pinfunction "1_1") (pintype "passive"))
    )
    (net (code "22") (name "Net-(C17-Pad1)") (class "Default")
      (node (ref "C17") (pin "1") (pinfunction "1_1") (pintype "passive"))
      (node (ref "R12") (pin "2") (pinfunction "2_2") (pintype "passive"))
      (node (ref "R14") (pin "1") (pinfunction "1_1") (pintype "passive"))
    )
    (net (code "23") (name "Net-(C23-Pad1)") (class "Default")
      (node (ref "C23") (pin "1") (pinfunction "1_1") (pintype "passive"))
      (node (ref "R15") (pin "1") (pinfunction "1_1") (pintype "passive"))
    )
    (net (code "24") (name "Net-(D1-A)") (class "Default")
      (node (ref "D1") (pin "1") (pinfunction "A_1") (pintype "passive"))
      (node (ref "L2") (pin "2") (pinfunction "2_2") (pintype "passive"))
      (node (ref "U2") (pin "1") (pinfunction "INP_2_1") (pintype "power_in"))
      (node (ref "U2") (pin "24") (pinfunction "INP_24") (pintype "power_in"))
    )
    (net (code "25") (name "Net-(D1-C)") (class "Default")
      (node (ref "C13") (pin "2") (pinfunction "2_2") (pintype "passive"))
      (node (ref "C18") (pin "1") (pinfunction "1_1") (pintype "passive"))
      (node (ref "C21") (pin "1") (pinfunction "1_1") (pintype "passive"))
      (node (ref "D1") (pin "2") (pinfunction "C_2") (pintype "passive"))
      (node (ref "R16") (pin "1") (pinfunction "1_1") (pintype "passive"))
      (node (ref "R7") (pin "1") (pinfunction "1_1") (pintype "passive"))
      (node (ref "U2") (pin "23") (pinfunction "VPOS_23") (pintype "input"))
    )
    (net (code "26") (name "Net-(D2-A)") (class "Default")
      (node (ref "C12") (pin "2") (pinfunction "2_2") (pintype "passive"))
      (node (ref "C19") (pin "2") (pinfunction "2_2") (pintype "passive"))
      (node (ref "C22") (pin "2") (pinfunction "2_2") (pintype "passive"))
      (node (ref "D2") (pin "1") (pinfunction "A_1") (pintype "passive"))
      (node (ref "R10") (pin "1") (pinfunction "1_1") (pintype "passive"))
      (node (ref "R17") (pin "1") (pinfunction "1_1") (pintype "passive"))
      (node (ref "U2") (pin "15") (pinfunction "VNEG_15") (pintype "input"))
    )
    (net (code "27") (name "Net-(D2-C)") (class "Default")
      (node (ref "D2") (pin "2") (pinfunction "C_2") (pintype "passive"))
      (node (ref "L3") (pin "1") (pinfunction "1_1") (pintype "passive"))
      (node (ref "U2") (pin "13") (pinfunction "OUTN_2_13") (pintype "power_in"))
      (node (ref "U2") (pin "14") (pinfunction "OUTN_14") (pintype "power_in"))
    )
    (net (code "28") (name "Net-(D3-A)") (class "Default")
      (node (ref "D3") (pin "1") (pinfunction "A_1") (pintype "passive"))
      (node (ref "L4") (pin "4") (pinfunction "4_4") (pintype "passive"))
      (node (ref "R15") (pin "2") (pinfunction "2_2") (pintype "passive"))
    )
    (net (code "29") (name "Net-(D3-C)") (class "Default")
      (node (ref "C23") (pin "2") (pinfunction "2_2") (pintype "passive"))
      (node (ref "C24") (pin "1") (pinfunction "1_1") (pintype "passive"))
      (node (ref "D3") (pin "2") (pinfunction "C_2") (pintype "passive"))
      (node (ref "L5") (pin "1") (pinfunction "1_1") (pintype "passive"))
    )
    (net (code "30") (name "Net-(D4-PadA)") (class "Default")
      (node (ref "D4") (pin "A") (pinfunction "A_A") (pintype "passive"))
      (node (ref "R19") (pin "2") (pinfunction "2_2") (pintype "passive"))
    )
    (net (code "31") (name "Net-(D5-PadA)") (class "Default")
      (node (ref "D5") (pin "A") (pinfunction "A_A") (pintype "passive"))
      (node (ref "R20") (pin "1") (pinfunction "1_1") (pintype "passive"))
    )
    (net (code "32") (name "Net-(D6-PadC)") (class "Default")
      (node (ref "D6") (pin "C") (pinfunction "C_C") (pintype "passive"))
      (node (ref "R18") (pin "2") (pinfunction "2_2") (pintype "passive"))
    )
    (net (code "33") (name "Net-(INB-K)") (class "Default")
      (node (ref "IN") (pin "2") (pinfunction "K_2") (pintype "passive"))
      (node (ref "R1") (pin "1") (pinfunction "1_1") (pintype "passive"))
    )
    (net (code "34") (name "Net-(J+15-Pad2)") (class "Default")
      (node (ref "J+15") (pin "2") (pinfunction "2_2") (pintype "passive"))
      (node (ref "R19") (pin "1") (pinfunction "1_1") (pintype "passive"))
    )
    (net (code "35") (name "Net-(J-15-Pad1)") (class "Default")
      (node (ref "J-15") (pin "1") (pinfunction "1_1") (pintype "passive"))
      (node (ref "R18") (pin "1") (pinfunction "1_1") (pintype "passive"))
    )
    (net (code "36") (name "Net-(J5-Pad2)") (class "Default")
      (node (ref "J5") (pin "2") (pinfunction "2_2") (pintype "passive"))
      (node (ref "R20") (pin "2") (pinfunction "2_2") (pintype "passive"))
    )
    (net (code "37") (name "Net-(L4-Pad2)") (class "Default")
      (node (ref "L4") (pin "2") (pinfunction "2_2") (pintype "passive"))
      (node (ref "R14") (pin "2") (pinfunction "2_2") (pintype "passive"))
    )
    (net (code "38") (name "Net-(U1-BST)") (class "Default")
      (node (ref "C8") (pin "1") (pinfunction "1_1") (pintype "passive"))
      (node (ref "U1") (pin "10") (pinfunction "BST_10") (pintype "power_in"))
    )
    (net (code "39") (name "Net-(U1-EN_UVLO)") (class "Default")
      (node (ref "R2") (pin "1") (pinfunction "1_1") (pintype "passive"))
      (node (ref "R3") (pin "2") (pinfunction "2_2") (pintype "passive"))
      (node (ref "U1") (pin "4") (pinfunction "EN_UVLO_4") (pintype "input"))
    )
    (net (code "40") (name "Net-(U1-FB)") (class "Default")
      (node (ref "C11") (pin "2") (pinfunction "2_2") (pintype "passive"))
      (node (ref "R12") (pin "1") (pinfunction "1_1") (pintype "passive"))
      (node (ref "R13") (pin "2") (pinfunction "2_2") (pintype "passive"))
      (node (ref "R9") (pin "2") (pinfunction "2_2") (pintype "passive"))
      (node (ref "U1") (pin "8") (pinfunction "FB_8") (pintype "input"))
    )
    (net (code "41") (name "Net-(U1-FPWM)") (class "Default")
      (node (ref "C9") (pin "1") (pinfunction "1_1") (pintype "passive"))
      (node (ref "U1") (pin "7") (pinfunction "FPWM_7") (pintype "input"))
      (node (ref "U1") (pin "9") (pinfunction "VCC_9") (pintype "power_in"))
    )
    (net (code "42") (name "Net-(U1-RON)") (class "Default")
      (node (ref "R5") (pin "2") (pinfunction "2_2") (pintype "passive"))
      (node (ref "U1") (pin "5") (pinfunction "RON_5") (pintype "input"))
    )
    (net (code "43") (name "Net-(U1-SS)") (class "Default")
      (node (ref "C7") (pin "1") (pinfunction "1_1") (pintype "passive"))
      (node (ref "U1") (pin "6") (pinfunction "SS_6") (pintype "input"))
    )
    (net (code "44") (name "Net-(U1-SW)") (class "Default")
      (node (ref "C8") (pin "2") (pinfunction "2_2") (pintype "passive"))
      (node (ref "L4") (pin "3") (pinfunction "3_3") (pintype "passive"))
      (node (ref "R8") (pin "1") (pinfunction "1_1") (pintype "passive"))
      (node (ref "U1") (pin "11") (pinfunction "SW_2_11") (pintype "power_in"))
      (node (ref "U1") (pin "12") (pinfunction "SW_12") (pintype "power_in"))
    )
    (net (code "45") (name "Net-(U1-VIN)") (class "Default")
      (node (ref "C2") (pin "1") (pinfunction "1_1") (pintype "passive"))
      (node (ref "C4") (pin "1") (pinfunction "1_1") (pintype "passive"))
      (node (ref "L1") (pin "2") (pinfunction "2_2") (pintype "passive"))
      (node (ref "R2") (pin "2") (pinfunction "2_2") (pintype "passive"))
      (node (ref "R5") (pin "1") (pinfunction "1_1") (pintype "passive"))
      (node (ref "U1") (pin "3") (pinfunction "VIN_3") (pintype "power_in"))
    )
    (net (code "46") (name "Net-(U2-CN)") (class "Default")
      (node (ref "C10") (pin "1") (pinfunction "1_1") (pintype "passive"))
      (node (ref "U2") (pin "18") (pinfunction "CN_18") (pintype "passive"))
    )
    (net (code "47") (name "Net-(U2-CP)") (class "Default")
      (node (ref "C15") (pin "1") (pinfunction "1_1") (pintype "passive"))
      (node (ref "U2") (pin "21") (pinfunction "CP_21") (pintype "passive"))
    )
    (net (code "48") (name "Net-(U2-ENN)") (class "Default")
      (node (ref "C6") (pin "1") (pinfunction "1_1") (pintype "passive"))
      (node (ref "R4") (pin "1") (pinfunction "1_1") (pintype "passive"))
      (node (ref "U2") (pin "10") (pinfunction "ENN_10") (pintype "input"))
      (node (ref "U2") (pin "11") (pinfunction "PSN_11") (pintype "input"))
      (node (ref "U2") (pin "4") (pinfunction "VIN_4") (pintype "power_in"))
      (node (ref "U2") (pin "8") (pinfunction "ENP_8") (pintype "input"))
      (node (ref "U2") (pin "9") (pinfunction "PSP_9") (pintype "input"))
    )
    (net (code "49") (name "Net-(U2-FBN)") (class "Default")
      (node (ref "C12") (pin "1") (pinfunction "1_1") (pintype "passive"))
      (node (ref "R10") (pin "2") (pinfunction "2_2") (pintype "passive"))
      (node (ref "R6") (pin "1") (pinfunction "1_1") (pintype "passive"))
      (node (ref "U2") (pin "16") (pinfunction "FBN_16") (pintype "input"))
    )
    (net (code "50") (name "Net-(U2-FBP)") (class "Default")
      (node (ref "C13") (pin "1") (pinfunction "1_1") (pintype "passive"))
      (node (ref "R11") (pin "2") (pinfunction "2_2") (pintype "passive"))
      (node (ref "R7") (pin "2") (pinfunction "2_2") (pintype "passive"))
      (node (ref "U2") (pin "22") (pinfunction "FBP_22") (pintype "input"))
    )
    (net (code "51") (name "Net-(U2-INN)") (class "Default")
      (node (ref "C3") (pin "1") (pinfunction "1_1") (pintype "passive"))
      (node (ref "C5") (pin "1") (pinfunction "1_1") (pintype "passive"))
      (node (ref "FB1") (pin "2") (pinfunction "2_2") (pintype "passive"))
      (node (ref "L2") (pin "1") (pinfunction "1_1") (pintype "passive"))
      (node (ref "R4") (pin "2") (pinfunction "2_2") (pintype "passive"))
      (node (ref "U2") (pin "5") (pinfunction "INN_2_5") (pintype "power_in"))
      (node (ref "U2") (pin "6") (pinfunction "INN_6") (pintype "power_in"))
    )
    (net (code "52") (name "Net-(U2-VREF)") (class "Default")
      (node (ref "C16") (pin "1") (pinfunction "1_1") (pintype "passive"))
      (node (ref "R6") (pin "2") (pinfunction "2_2") (pintype "passive"))
      (node (ref "U2") (pin "17") (pinfunction "VREF_17") (pintype "output"))
    )
    (net (code "53") (name "Net-(U3-BYPASS)") (class "Default")
      (node (ref "C31") (pin "1") (pinfunction "1_1") (pintype "passive"))
      (node (ref "U3") (pin "4") (pinfunction "BYPASS_4") (pintype "input"))
    )
    (net (code "54") (name "Net-(U3-EN)") (class "Default")
      (node (ref "J3V3") (pin "1") (pinfunction "1_1") (pintype "passive"))
      (node (ref "U3") (pin "1") (pinfunction "VIN_1") (pintype "input"))
      (node (ref "U3") (pin "3") (pinfunction "EN_3") (pintype "input"))
    )
    (net (code "55") (name "unconnected-(U2-BSW-Pad7)") (class "Default")
      (node (ref "U2") (pin "7") (pinfunction "BSW_7") (pintype "output"))
    )
    (net (code "56") (name "unconnected-(U2-NC-Pad20)") (class "Default")
      (node (ref "U2") (pin "20") (pinfunction "NC_20") (pintype "passive"))
    )
  )
)
